# nodemcu.net
KiCad netlist of a schematic drawn in EAGLE
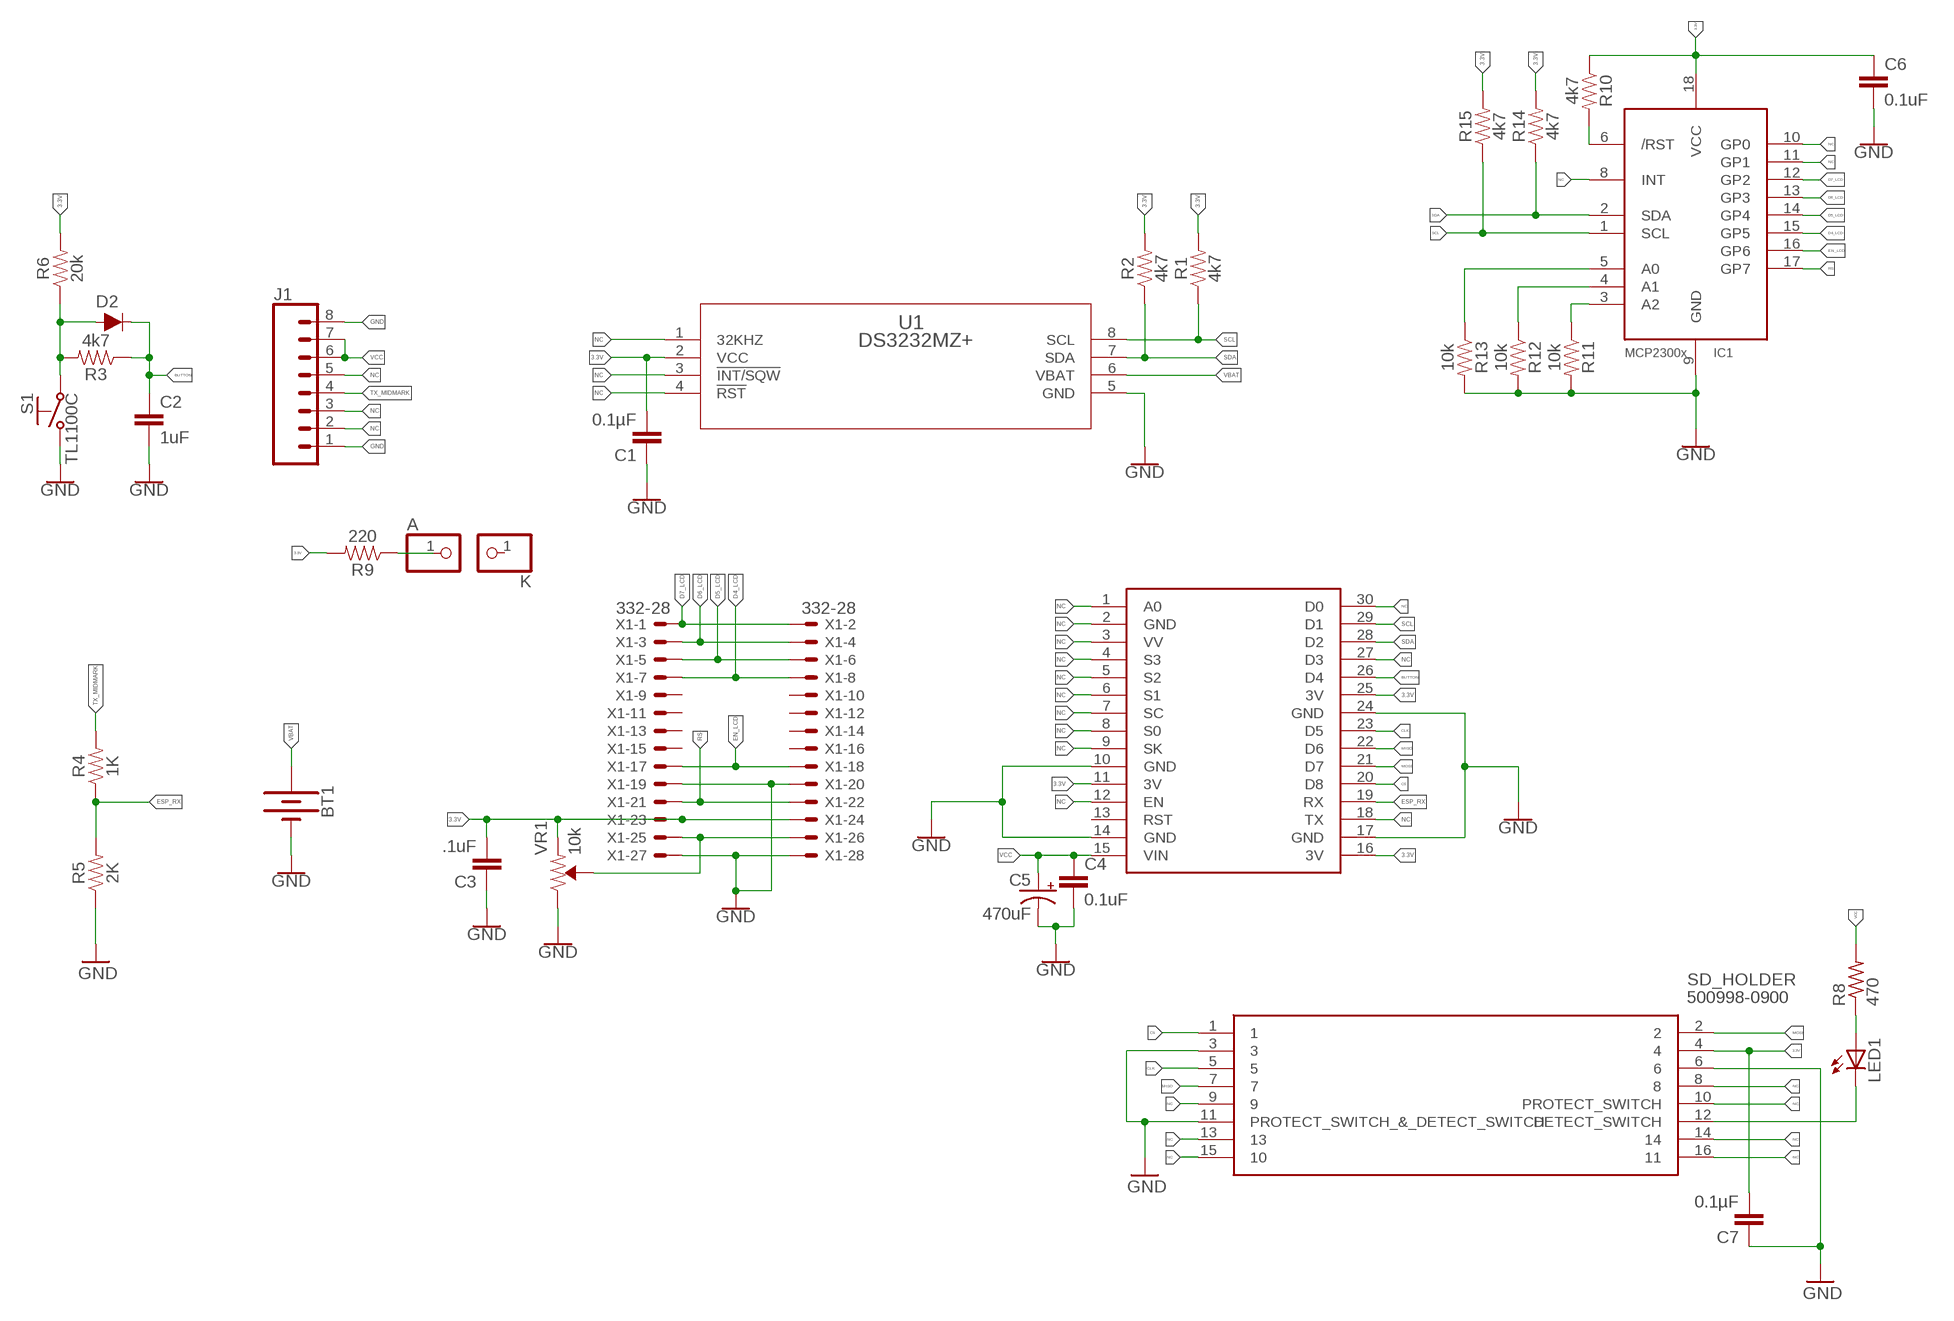
[diagram p0: schematic, sheet 1]

(export (version "E")
  (design (tool "Eeschema 10.0.6"))
  (components
    (comp (ref "A")
      (value "PINHD-1X1")
      (footprint "eagle-import:1X01")
      (libsource (lib "eagle-import") (part "PINHD-1X1"))
    )
    (comp (ref "BT1")
      (value "BATTERY-20MM_PTH")
      (footprint "eagle-import:BATTCOM_20MM_PTH")
      (libsource (lib "eagle-import") (part "BATTERY-20MM_PTH"))
    )
    (comp (ref "C1")
      (value "0.1µF")
      (footprint "eagle-import:0805")
      (libsource (lib "eagle-import") (part "0.33UF/330NF-0805-50V-10%"))
    )
    (comp (ref "C2")
      (value "1uF")
      (footprint "eagle-import:0805")
      (libsource (lib "eagle-import") (part "1.0UF-0805-25V-10%"))
    )
    (comp (ref "C3")
      (value ".1uF")
      (footprint "eagle-import:0805")
      (libsource (lib "eagle-import") (part "1.0UF-0805-25V-10%"))
    )
    (comp (ref "C4")
      (value "0.1uF")
      (footprint "eagle-import:0805")
      (libsource (lib "eagle-import") (part "1.0UF-0805-25V-10%"))
    )
    (comp (ref "C5")
      (value "470uF")
      (footprint "eagle-import:NIC_10X10.5_CAP")
      (libsource (lib "eagle-import") (part "100UF-POLAR-10X10.5-63V-20%"))
    )
    (comp (ref "C6")
      (value "0.1uF")
      (footprint "eagle-import:0805")
      (libsource (lib "eagle-import") (part "1.0UF-0805-25V-10%"))
    )
    (comp (ref "C7")
      (value "0.1µF")
      (footprint "eagle-import:0805")
      (libsource (lib "eagle-import") (part "0.33UF/330NF-0805-50V-10%"))
    )
    (comp (ref "D2")
      (value "1A/50V/1.1V")
      (footprint "eagle-import:DIODE-1N4001")
      (libsource (lib "eagle-import") (part "DIODE-PTH"))
    )
    (comp (ref "IC1")
      (value "MCP23008/P")
      (footprint "eagle-import:DIL18")
      (libsource (lib "eagle-import") (part "MCP23008/P"))
    )
    (comp (ref "J1")
      (value "CONN_08\"")
      (footprint "eagle-import:1X08")
      (libsource (lib "eagle-import") (part "CONN_08{dblquote}"))
    )
    (comp (ref "K")
      (value "PINHD-1X1")
      (footprint "eagle-import:1X01")
      (libsource (lib "eagle-import") (part "PINHD-1X1"))
    )
    (comp (ref "LED1")
      (value "LEDSIDELED")
      (footprint "eagle-import:OSRAM-SIDELED")
      (libsource (lib "eagle-import") (part "LEDSIDELED"))
    )
    (comp (ref "R1")
      (value "4k7")
      (footprint "eagle-import:0805")
      (libsource (lib "eagle-import") (part "0.22OHM-0805-1/4W-1%"))
    )
    (comp (ref "R2")
      (value "4k7")
      (footprint "eagle-import:0805")
      (libsource (lib "eagle-import") (part "0.22OHM-0805-1/4W-1%"))
    )
    (comp (ref "R3")
      (value "4k7")
      (footprint "eagle-import:0805")
      (libsource (lib "eagle-import") (part "0.22OHM-0805-1/4W-1%"))
    )
    (comp (ref "R4")
      (value "1K")
      (footprint "eagle-import:0805")
      (libsource (lib "eagle-import") (part "0.22OHM-0805-1/4W-1%"))
    )
    (comp (ref "R5")
      (value "2K")
      (footprint "eagle-import:0805")
      (libsource (lib "eagle-import") (part "0.22OHM-0805-1/4W-1%"))
    )
    (comp (ref "R6")
      (value "20k")
      (footprint "eagle-import:0805")
      (libsource (lib "eagle-import") (part "0.22OHM-0805-1/4W-1%"))
    )
    (comp (ref "R8")
      (value "470")
      (footprint "eagle-import:R0805")
      (libsource (lib "eagle-import") (part "R-US_R0805"))
    )
    (comp (ref "R9")
      (value "220")
      (footprint "eagle-import:0805")
      (libsource (lib "eagle-import") (part "0.22OHM-0805-1/4W-1%"))
    )
    (comp (ref "R10")
      (value "4k7")
      (footprint "eagle-import:0805")
      (libsource (lib "eagle-import") (part "0.22OHM-0805-1/4W-1%"))
    )
    (comp (ref "R11")
      (value "10k")
      (footprint "eagle-import:0805")
      (libsource (lib "eagle-import") (part "0.22OHM-0805-1/4W-1%"))
    )
    (comp (ref "R12")
      (value "10k")
      (footprint "eagle-import:0805")
      (libsource (lib "eagle-import") (part "0.22OHM-0805-1/4W-1%"))
    )
    (comp (ref "R13")
      (value "10k")
      (footprint "eagle-import:0805")
      (libsource (lib "eagle-import") (part "0.22OHM-0805-1/4W-1%"))
    )
    (comp (ref "R14")
      (value "4k7")
      (footprint "eagle-import:0805")
      (libsource (lib "eagle-import") (part "0.22OHM-0805-1/4W-1%"))
    )
    (comp (ref "R15")
      (value "4k7")
      (footprint "eagle-import:0805")
      (libsource (lib "eagle-import") (part "0.22OHM-0805-1/4W-1%"))
    )
    (comp (ref "S1")
      (value "TL1100C")
      (footprint "eagle-import:TL1100C")
      (libsource (lib "eagle-import") (part "TL1100C"))
    )
    (comp (ref "SD_HOLDER")
      (value "500998-0900")
      (footprint "eagle-import:5009980900")
      (fields (field (name "MOUSER_PART_NUMBER") "538-500998-0900") (field (name "RS_PART_NUMBER") "4879327"))
      (libsource (lib "eagle-import") (part "500998-0900"))
    )
    (comp (ref "U$1")
      (value "NODEMCU")
      (footprint "eagle-import:NODEMCU")
      (libsource (lib "eagle-import") (part "NODEMCU"))
    )
    (comp (ref "U1")
      (value "DS3232MZ+")
      (footprint "eagle-import:21-0041B_8")
      (libsource (lib "eagle-import") (part "DS3232MZ+"))
    )
    (comp (ref "VR1")
      (value "10k")
      (footprint "eagle-import:TRIMPOT-PTH-3386U")
      (libsource (lib "eagle-import") (part "TRIMPOT-PTH-10MM-KNOB-1/2W-10%"))
    )
    (comp (ref "X1")
      (value "332-28")
      (footprint "eagle-import:332-28")
      (libsource (lib "eagle-import") (part "332-28"))
    )
  )
  (nets
    (net (code "1") (name "3.3V") (class "Default")
      (node (ref "C1") (pin "2") (pinfunction "2_2") (pintype "passive"))
      (node (ref "C3") (pin "2") (pinfunction "2_2") (pintype "passive"))
      (node (ref "C6") (pin "1") (pinfunction "1_1") (pintype "passive"))
      (node (ref "C7") (pin "2") (pinfunction "2_2") (pintype "passive"))
      (node (ref "IC1") (pin "18") (pinfunction "VCC_18") (pintype "power_in"))
      (node (ref "R1") (pin "2") (pinfunction "2_2") (pintype "passive"))
      (node (ref "R10") (pin "1") (pinfunction "1_1") (pintype "passive"))
      (node (ref "R14") (pin "2") (pinfunction "2_2") (pintype "passive"))
      (node (ref "R15") (pin "2") (pinfunction "2_2") (pintype "passive"))
      (node (ref "R2") (pin "2") (pinfunction "2_2") (pintype "passive"))
      (node (ref "R6") (pin "2") (pinfunction "2_2") (pintype "passive"))
      (node (ref "R9") (pin "2") (pinfunction "2_2") (pintype "passive"))
      (node (ref "SD_HOLDER") (pin "4") (pinfunction "4_4") (pintype "bidirectional"))
      (node (ref "U$1") (pin "11") (pinfunction "3V_11") (pintype "power_in"))
      (node (ref "U$1") (pin "16") (pinfunction "3V_16") (pintype "power_in"))
      (node (ref "U$1") (pin "25") (pinfunction "3V_25") (pintype "power_in"))
      (node (ref "U1") (pin "2") (pinfunction "VCC_2") (pintype "power_in"))
      (node (ref "VR1") (pin "1") (pinfunction "CCW_1") (pintype "passive"))
      (node (ref "X1") (pin "23") (pinfunction "S_23") (pintype "passive"))
      (node (ref "X1") (pin "24") (pinfunction "S_24") (pintype "passive"))
    )
    (net (code "2") (name "BUTTON") (class "Default")
      (node (ref "C2") (pin "1") (pinfunction "1_1") (pintype "passive"))
      (node (ref "D2") (pin "A") (pinfunction "A_A") (pintype "passive"))
      (node (ref "D2") (pin "C") (pinfunction "C_C") (pintype "passive"))
      (node (ref "R3") (pin "1") (pinfunction "1_1") (pintype "passive"))
      (node (ref "R3") (pin "2") (pinfunction "2_2") (pintype "passive"))
      (node (ref "R6") (pin "1") (pinfunction "1_1") (pintype "passive"))
      (node (ref "S1") (pin "1") (pinfunction "P_1") (pintype "passive"))
      (node (ref "U$1") (pin "26") (pinfunction "D4_26") (pintype "bidirectional"))
    )
    (net (code "3") (name "CLK") (class "Default")
      (node (ref "SD_HOLDER") (pin "5") (pinfunction "5_5") (pintype "bidirectional"))
      (node (ref "U$1") (pin "23") (pinfunction "D5_23") (pintype "bidirectional"))
    )
    (net (code "4") (name "CS") (class "Default")
      (node (ref "SD_HOLDER") (pin "1") (pinfunction "1_1") (pintype "bidirectional"))
      (node (ref "U$1") (pin "20") (pinfunction "D8_20") (pintype "bidirectional"))
    )
    (net (code "5") (name "D4_LCD") (class "Default")
      (node (ref "IC1") (pin "15") (pinfunction "GP5_15") (pintype "bidirectional"))
      (node (ref "X1") (pin "7") (pinfunction "S_7") (pintype "passive"))
      (node (ref "X1") (pin "8") (pinfunction "S_8") (pintype "passive"))
    )
    (net (code "6") (name "D5_LCD") (class "Default")
      (node (ref "IC1") (pin "14") (pinfunction "GP4_14") (pintype "bidirectional"))
      (node (ref "X1") (pin "5") (pinfunction "S_5") (pintype "passive"))
      (node (ref "X1") (pin "6") (pinfunction "S_6") (pintype "passive"))
    )
    (net (code "7") (name "D6_LCD") (class "Default")
      (node (ref "IC1") (pin "13") (pinfunction "GP3_13") (pintype "bidirectional"))
      (node (ref "X1") (pin "3") (pinfunction "S_3") (pintype "passive"))
      (node (ref "X1") (pin "4") (pinfunction "S_4") (pintype "passive"))
    )
    (net (code "8") (name "D7_LCD") (class "Default")
      (node (ref "IC1") (pin "12") (pinfunction "GP2_12") (pintype "bidirectional"))
      (node (ref "X1") (pin "1") (pinfunction "S_1") (pintype "passive"))
      (node (ref "X1") (pin "2") (pinfunction "S_2") (pintype "passive"))
    )
    (net (code "9") (name "EN_LCD") (class "Default")
      (node (ref "IC1") (pin "16") (pinfunction "GP6_16") (pintype "bidirectional"))
      (node (ref "X1") (pin "17") (pinfunction "S_17") (pintype "passive"))
      (node (ref "X1") (pin "18") (pinfunction "S_18") (pintype "passive"))
    )
    (net (code "10") (name "ESP_RX") (class "Default")
      (node (ref "R4") (pin "1") (pinfunction "1_1") (pintype "passive"))
      (node (ref "R5") (pin "2") (pinfunction "2_2") (pintype "passive"))
      (node (ref "U$1") (pin "19") (pinfunction "RX_19") (pintype "bidirectional"))
    )
    (net (code "11") (name "GND") (class "Default")
      (node (ref "BT1") (pin "2") (pinfunction "-_2") (pintype "power_in"))
      (node (ref "C1") (pin "1") (pinfunction "1_1") (pintype "passive"))
      (node (ref "C2") (pin "2") (pinfunction "2_2") (pintype "passive"))
      (node (ref "C3") (pin "1") (pinfunction "1_1") (pintype "passive"))
      (node (ref "C4") (pin "2") (pinfunction "2_2") (pintype "passive"))
      (node (ref "C5") (pin "-") (pinfunction "-_-") (pintype "passive"))
      (node (ref "C6") (pin "2") (pinfunction "2_2") (pintype "passive"))
      (node (ref "C7") (pin "1") (pinfunction "1_1") (pintype "passive"))
      (node (ref "IC1") (pin "9") (pinfunction "GND_9") (pintype "power_in"))
      (node (ref "J1") (pin "1") (pinfunction "1_1") (pintype "passive"))
      (node (ref "J1") (pin "8") (pinfunction "8_8") (pintype "passive"))
      (node (ref "R11") (pin "2") (pinfunction "2_2") (pintype "passive"))
      (node (ref "R12") (pin "2") (pinfunction "2_2") (pintype "passive"))
      (node (ref "R13") (pin "2") (pinfunction "2_2") (pintype "passive"))
      (node (ref "R5") (pin "1") (pinfunction "1_1") (pintype "passive"))
      (node (ref "S1") (pin "2") (pinfunction "S_2") (pintype "passive"))
      (node (ref "SD_HOLDER") (pin "11") (pinfunction "PROTECT_SWITCH_&_DETECT_SWITCH_11") (pintype "bidirectional"))
      (node (ref "SD_HOLDER") (pin "3") (pinfunction "3_3") (pintype "bidirectional"))
      (node (ref "SD_HOLDER") (pin "6") (pinfunction "6_6") (pintype "bidirectional"))
      (node (ref "U$1") (pin "10") (pinfunction "GND_10") (pintype "power_in"))
      (node (ref "U$1") (pin "14") (pinfunction "GND_14") (pintype "power_in"))
      (node (ref "U$1") (pin "17") (pinfunction "GND_17") (pintype "power_in"))
      (node (ref "U$1") (pin "24") (pinfunction "GND_24") (pintype "power_in"))
      (node (ref "U1") (pin "5") (pinfunction "GND_5") (pintype "power_in"))
      (node (ref "VR1") (pin "3") (pinfunction "CW_3") (pintype "passive"))
      (node (ref "X1") (pin "19") (pinfunction "S_19") (pintype "passive"))
      (node (ref "X1") (pin "20") (pinfunction "S_20") (pintype "passive"))
      (node (ref "X1") (pin "27") (pinfunction "S_27") (pintype "passive"))
      (node (ref "X1") (pin "28") (pinfunction "S_28") (pintype "passive"))
    )
    (net (code "12") (name "MISO") (class "Default")
      (node (ref "SD_HOLDER") (pin "7") (pinfunction "7_7") (pintype "bidirectional"))
      (node (ref "U$1") (pin "22") (pinfunction "D6_22") (pintype "bidirectional"))
    )
    (net (code "13") (name "MOSI") (class "Default")
      (node (ref "SD_HOLDER") (pin "2") (pinfunction "2_2") (pintype "bidirectional"))
      (node (ref "U$1") (pin "21") (pinfunction "D7_21") (pintype "bidirectional"))
    )
    (net (code "14") (name "NC") (class "Default")
      (node (ref "IC1") (pin "10") (pinfunction "GP0_10") (pintype "bidirectional"))
      (node (ref "IC1") (pin "11") (pinfunction "GP1_11") (pintype "bidirectional"))
      (node (ref "IC1") (pin "8") (pinfunction "INT_8") (pintype "output"))
      (node (ref "J1") (pin "2") (pinfunction "2_2") (pintype "passive"))
      (node (ref "J1") (pin "3") (pinfunction "3_3") (pintype "passive"))
      (node (ref "J1") (pin "5") (pinfunction "5_5") (pintype "passive"))
      (node (ref "SD_HOLDER") (pin "10") (pinfunction "PROTECT_SWITCH_10") (pintype "bidirectional"))
      (node (ref "SD_HOLDER") (pin "13") (pinfunction "13_13") (pintype "bidirectional"))
      (node (ref "SD_HOLDER") (pin "14") (pinfunction "14_14") (pintype "bidirectional"))
      (node (ref "SD_HOLDER") (pin "15") (pinfunction "10_15") (pintype "bidirectional"))
      (node (ref "SD_HOLDER") (pin "16") (pinfunction "11_16") (pintype "bidirectional"))
      (node (ref "SD_HOLDER") (pin "8") (pinfunction "8_8") (pintype "bidirectional"))
      (node (ref "SD_HOLDER") (pin "9") (pinfunction "9_9") (pintype "bidirectional"))
      (node (ref "U$1") (pin "1") (pinfunction "A0_1") (pintype "bidirectional"))
      (node (ref "U$1") (pin "12") (pinfunction "EN_12") (pintype "bidirectional"))
      (node (ref "U$1") (pin "18") (pinfunction "TX_18") (pintype "bidirectional"))
      (node (ref "U$1") (pin "27") (pinfunction "D3_27") (pintype "bidirectional"))
      (node (ref "U$1") (pin "30") (pinfunction "D0_30") (pintype "bidirectional"))
      (node (ref "U$1") (pin "4") (pinfunction "S3_4") (pintype "bidirectional"))
      (node (ref "U$1") (pin "5") (pinfunction "S2_5") (pintype "bidirectional"))
      (node (ref "U$1") (pin "6") (pinfunction "S1_6") (pintype "bidirectional"))
      (node (ref "U$1") (pin "7") (pinfunction "SC_7") (pintype "bidirectional"))
      (node (ref "U$1") (pin "8") (pinfunction "S0_8") (pintype "bidirectional"))
      (node (ref "U$1") (pin "9") (pinfunction "SK_9") (pintype "bidirectional"))
      (node (ref "U1") (pin "1") (pinfunction "32KHZ_1") (pintype "passive"))
      (node (ref "U1") (pin "3") (pinfunction "~{INT/SQW}_3") (pintype "passive"))
      (node (ref "U1") (pin "4") (pinfunction "~{RST}_4") (pintype "passive"))
    )
    (net (code "15") (name "Net-(A-Pad1)") (class "Default")
      (node (ref "A") (pin "1") (pinfunction "1_1") (pintype "passive"))
      (node (ref "R9") (pin "1") (pinfunction "1_1") (pintype "passive"))
    )
    (net (code "16") (name "Net-(IC1-A0)") (class "Default")
      (node (ref "IC1") (pin "5") (pinfunction "A0_5") (pintype "input"))
      (node (ref "R13") (pin "1") (pinfunction "1_1") (pintype "passive"))
    )
    (net (code "17") (name "Net-(IC1-A1)") (class "Default")
      (node (ref "IC1") (pin "4") (pinfunction "A1_4") (pintype "input"))
      (node (ref "R12") (pin "1") (pinfunction "1_1") (pintype "passive"))
    )
    (net (code "18") (name "Net-(IC1-A2)") (class "Default")
      (node (ref "IC1") (pin "3") (pinfunction "A2_3") (pintype "input"))
      (node (ref "R11") (pin "1") (pinfunction "1_1") (pintype "passive"))
    )
    (net (code "19") (name "Net-(IC1-{slash}RST)") (class "Default")
      (node (ref "IC1") (pin "6") (pinfunction "/RST_6") (pintype "input"))
      (node (ref "R10") (pin "2") (pinfunction "2_2") (pintype "passive"))
    )
    (net (code "20") (name "Net-(LED1-PadA)") (class "Default")
      (node (ref "LED1") (pin "A") (pinfunction "A_A") (pintype "passive"))
      (node (ref "R8") (pin "1") (pinfunction "1_1") (pintype "passive"))
    )
    (net (code "21") (name "Net-(SD_HOLDER-DETECT_SWITCH)") (class "Default")
      (node (ref "LED1") (pin "C") (pinfunction "C_C") (pintype "passive"))
      (node (ref "SD_HOLDER") (pin "12") (pinfunction "DETECT_SWITCH_12") (pintype "bidirectional"))
    )
    (net (code "22") (name "Net-(VR1-WIPER)") (class "Default")
      (node (ref "VR1") (pin "2") (pinfunction "WIPER_2") (pintype "passive"))
      (node (ref "X1") (pin "25") (pinfunction "S_25") (pintype "passive"))
      (node (ref "X1") (pin "26") (pinfunction "S_26") (pintype "passive"))
    )
    (net (code "23") (name "RS") (class "Default")
      (node (ref "IC1") (pin "17") (pinfunction "GP7_17") (pintype "bidirectional"))
      (node (ref "X1") (pin "21") (pinfunction "S_21") (pintype "passive"))
      (node (ref "X1") (pin "22") (pinfunction "S_22") (pintype "passive"))
    )
    (net (code "24") (name "SCL") (class "Default")
      (node (ref "IC1") (pin "1") (pinfunction "SCL_1") (pintype "bidirectional"))
      (node (ref "R1") (pin "1") (pinfunction "1_1") (pintype "passive"))
      (node (ref "R15") (pin "1") (pinfunction "1_1") (pintype "passive"))
      (node (ref "U$1") (pin "29") (pinfunction "D1_29") (pintype "bidirectional"))
      (node (ref "U1") (pin "8") (pinfunction "SCL_8") (pintype "passive"))
    )
    (net (code "25") (name "SDA") (class "Default")
      (node (ref "IC1") (pin "2") (pinfunction "SDA_2") (pintype "bidirectional"))
      (node (ref "R14") (pin "1") (pinfunction "1_1") (pintype "passive"))
      (node (ref "R2") (pin "1") (pinfunction "1_1") (pintype "passive"))
      (node (ref "U$1") (pin "28") (pinfunction "D2_28") (pintype "bidirectional"))
      (node (ref "U1") (pin "7") (pinfunction "SDA_7") (pintype "passive"))
    )
    (net (code "26") (name "TX_MIDMARK") (class "Default")
      (node (ref "J1") (pin "4") (pinfunction "4_4") (pintype "passive"))
      (node (ref "R4") (pin "2") (pinfunction "2_2") (pintype "passive"))
    )
    (net (code "27") (name "VBAT") (class "Default")
      (node (ref "BT1") (pin "1") (pinfunction "+_1") (pintype "power_in"))
      (node (ref "U1") (pin "6") (pinfunction "VBAT_6") (pintype "power_in"))
    )
    (net (code "28") (name "VCC") (class "Default")
      (node (ref "C4") (pin "1") (pinfunction "1_1") (pintype "passive"))
      (node (ref "C5") (pin "+") (pinfunction "+_+") (pintype "passive"))
      (node (ref "J1") (pin "6") (pinfunction "6_6") (pintype "passive"))
      (node (ref "J1") (pin "7") (pinfunction "7_7") (pintype "passive"))
      (node (ref "R8") (pin "2") (pinfunction "2_2") (pintype "passive"))
      (node (ref "U$1") (pin "15") (pinfunction "VIN_15") (pintype "bidirectional"))
    )
    (net (code "29") (name "unconnected-(K-Pad1)") (class "Default")
      (node (ref "K") (pin "1") (pinfunction "1_1") (pintype "passive"))
    )
    (net (code "30") (name "unconnected-(U$1-GND-Pad2)") (class "Default")
      (node (ref "U$1") (pin "2") (pinfunction "GND_2") (pintype "power_in"))
    )
    (net (code "31") (name "unconnected-(U$1-RST-Pad13)") (class "Default")
      (node (ref "U$1") (pin "13") (pinfunction "RST_13") (pintype "bidirectional"))
    )
    (net (code "32") (name "unconnected-(U$1-VV-Pad3)") (class "Default")
      (node (ref "U$1") (pin "3") (pinfunction "VV_3") (pintype "bidirectional"))
    )
    (net (code "33") (name "unconnected-(X1AB-S-Pad9)") (class "Default")
      (node (ref "X1") (pin "9") (pinfunction "S_9") (pintype "passive"))
    )
    (net (code "34") (name "unconnected-(X1B-S-Pad10)") (class "Default")
      (node (ref "X1") (pin "10") (pinfunction "S_10") (pintype "passive"))
    )
    (net (code "35") (name "unconnected-(X1C-S-Pad11)") (class "Default")
      (node (ref "X1") (pin "11") (pinfunction "S_11") (pintype "passive"))
    )
    (net (code "36") (name "unconnected-(X1D-S-Pad12)") (class "Default")
      (node (ref "X1") (pin "12") (pinfunction "S_12") (pintype "passive"))
    )
    (net (code "37") (name "unconnected-(X1E-S-Pad13)") (class "Default")
      (node (ref "X1") (pin "13") (pinfunction "S_13") (pintype "passive"))
    )
    (net (code "38") (name "unconnected-(X1F-S-Pad14)") (class "Default")
      (node (ref "X1") (pin "14") (pinfunction "S_14") (pintype "passive"))
    )
    (net (code "39") (name "unconnected-(X1G-S-Pad15)") (class "Default")
      (node (ref "X1") (pin "15") (pinfunction "S_15") (pintype "passive"))
    )
    (net (code "40") (name "unconnected-(X1H-S-Pad16)") (class "Default")
      (node (ref "X1") (pin "16") (pinfunction "S_16") (pintype "passive"))
    )
  )
)
